# BRD9057A_SiWx917M_4-Layer_ExtSw_REF_DES_.net
KiCad netlist of a schematic drawn in Altium Designer
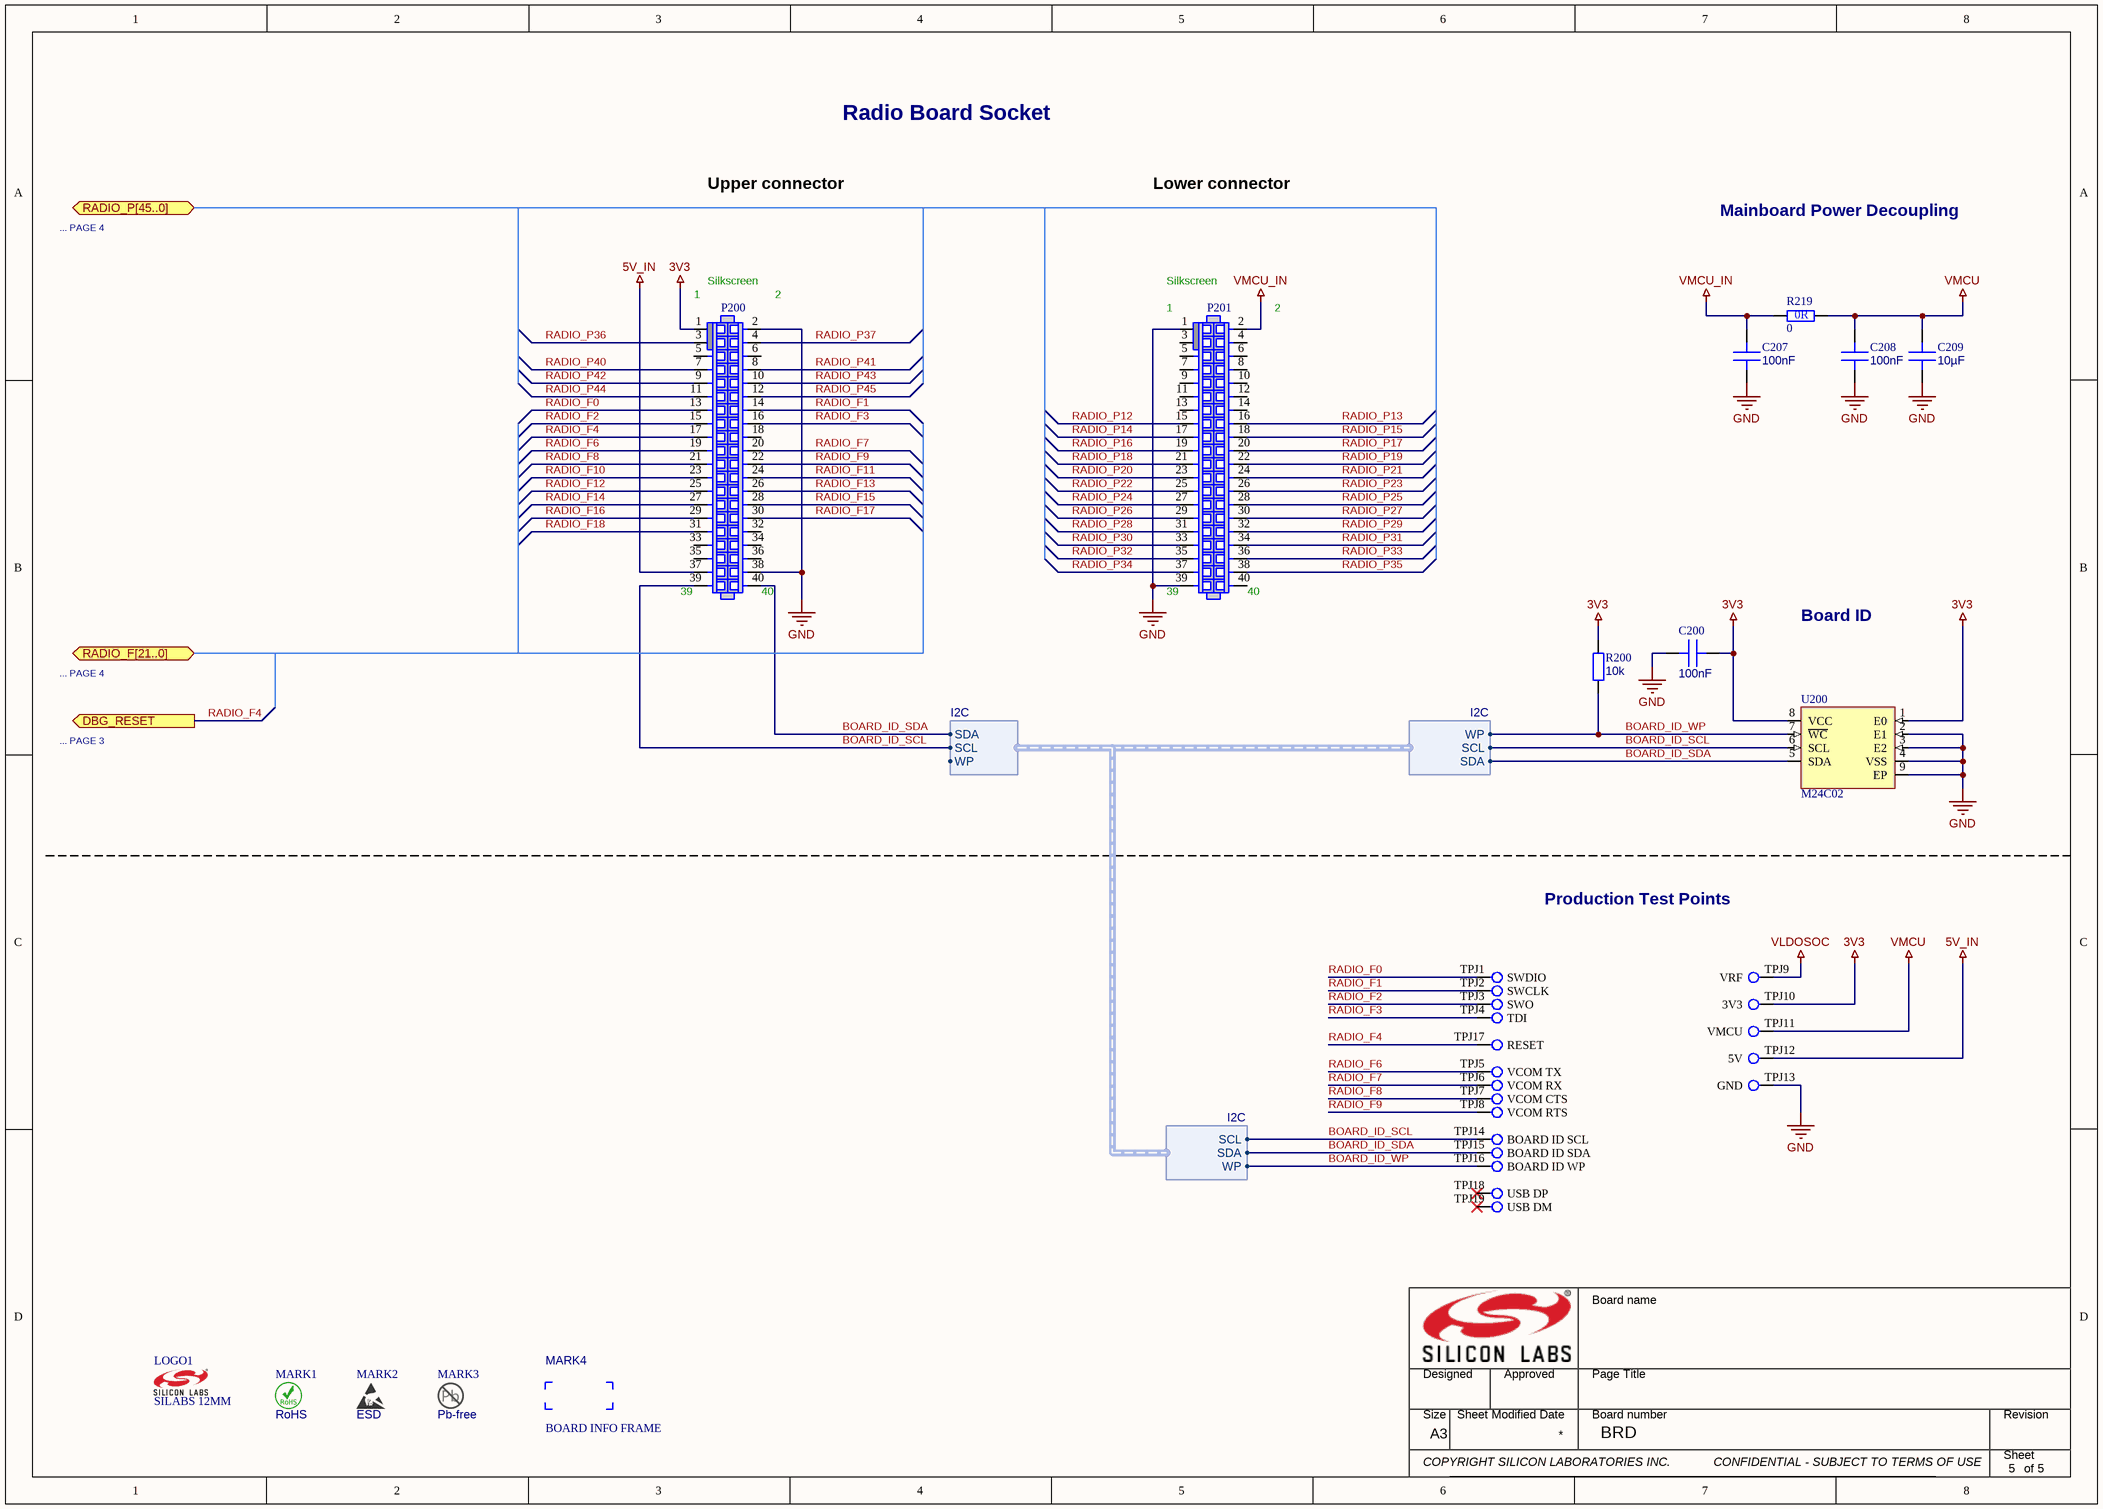
[diagram p0: BRD9057A_SiWx917M_4-Layer_ExtSw_REF_DES_A01_Page_5.SchDoc]

(export (version "E")
  (design (tool "Eeschema 10.0.6"))
  (components
    (comp (ref "C200")
      (value "100nF")
      (footprint "C0201_GM")
      (description "CAP CER 0201 X5R 100nF 16V 10%")
      (fields (field (name "TOLERANCE") "10%"))
      (libsource (lib "SiLabs Production Server") (part "Capacitor"))
    )
    (comp (ref "C207")
      (value "100nF")
      (footprint "C0201_GM")
      (description "CAP CER 0201 X5R 100nF 16V 10%")
      (fields (field (name "TOLERANCE") "10%"))
      (libsource (lib "SiLabs Production Server") (part "Capacitor"))
    )
    (comp (ref "C208")
      (value "100nF")
      (footprint "C0201_GM")
      (description "CAP CER 0201 X5R 100nF 16V 10%")
      (fields (field (name "TOLERANCE") "10%"))
      (libsource (lib "SiLabs Production Server") (part "Capacitor"))
    )
    (comp (ref "C209")
      (value "10µF")
      (footprint "C0603")
      (description "CAP CER 0603 X5R 10uF 16V 10%")
      (fields (field (name "TOLERANCE") "10%"))
      (libsource (lib "SiLabs Production Server") (part "Capacitor"))
    )
    (comp (ref "LOGO1")
      (value "SILABS 12MM")
      (footprint "LOGO_SILABS_W12.0_SILK")
      (description "Silkscreen logo, Silabs logo and text, B: 12MM, H:6MM")
      (fields (field (name "Comment") "LOGO SILABS 12MM"))
      (libsource (lib "SiLabs Production Server") (part "LOGO SILABS"))
    )
    (comp (ref "M1")
      (value "RB TEST FIXTURE PATTERN")
      (footprint "RB TEST FIXTURE PATTERN")
      (description "Subset of testpoints and keepouts for production test of Radio Boards")
      (libsource (lib "SiLabs Production Server") (part "RB FIXTURE PATTERN"))
    )
    (comp (ref "MARK1")
      (value "RoHS")
      (footprint "LOGO RoHS 5MM")
      (description "Silkscreen logo, RoHS, 5MM")
      (fields (field (name "Comment") "LOGO RoHS 5MM"))
      (libsource (lib "SiLabs Production Server") (part "LOGO RoHS"))
    )
    (comp (ref "MARK2")
      (value "ESD")
      (footprint "LOGO ESD 4.5MM")
      (description "Silkscreen logo, ESD, 4.5MM")
      (fields (field (name "Comment") "LOGO ESD 4.5MM"))
      (libsource (lib "SiLabs Production Server") (part "LOGO ESD"))
    )
    (comp (ref "MARK3")
      (value "Pb-free")
      (footprint "LOGO PBF 2MM")
      (description "Silkscreen logo, lead free, 2MM")
      (fields (field (name "Comment") "LOGO PBF 2MM"))
      (libsource (lib "SiLabs Production Server") (part "LOGO PBF"))
    )
    (comp (ref "MARK4")
      (value "BOARD INFO FRAME")
      (footprint "BOARD INFO FRAME SILK-Footprint-1")
      (description "Board info frame 19MM x 6MM, Silkscreen")
      (fields (field (name "Comment") "BOARD INFO FRAME 19MM"))
      (libsource (lib "SiLabs Production Server") (part "BOARD INFO FRAME"))
    )
    (comp (ref "P200")
      (value "2344-220MS3CUNR8")
      (footprint "SAMTEC_SFC-120-T2-L-D-A")
      (description "SOCKET 2X20 1.27MM SMD VRT KEYED")
      (fields (field (name "MANUFACTURER") "WCON"))
      (libsource (lib "SiLabs Production Server") (part "Header Female 2X20 with Notch"))
    )
    (comp (ref "P201")
      (value "2344-220MS3CUNR8")
      (footprint "SAMTEC_SFC-120-T2-L-D-A")
      (description "SOCKET 2X20 1.27MM SMD VRT KEYED")
      (fields (field (name "MANUFACTURER") "WCON"))
      (libsource (lib "SiLabs Production Server") (part "Header Female 2X20 with Notch"))
    )
    (comp (ref "R200")
      (value "10k")
      (footprint "R0201")
      (description "RES 0201 10K 1/20W 1% 200ppm")
      (fields (field (name "TOLERANCE") "1%"))
      (libsource (lib "SiLabs Production Server") (part "Resistor"))
    )
    (comp (ref "R219")
      (value "0")
      (footprint "R0402")
      (description "RES 0402 0R")
      (fields (field (name "TOLERANCE") "0%"))
      (libsource (lib "SiLabs Production Server") (part "Resistor-Jumper"))
    )
    (comp (ref "U200")
      (value "M24C02")
      (footprint "DFN50P300X200X60_HS-9N_GM")
      (description "IC EEPROM 2KBIT I2C UFDFPN8")
      (fields (field (name "VOLTAGE") "5.5V") (field (name "MANUFACTURER") "ST Microelectronics"))
      (libsource (lib "SiLabs Production Server") (part "M24C02-F"))
    )
  )
  (nets
    (net (code "6") (name "/BOARD_ID_SCL") (class "Default")
      (node (ref "M1") (pin "TPJ14") (pinfunction "BOARD_ID_SCL_TPJ14") (pintype "passive"))
      (node (ref "P200") (pin "39") (pinfunction "39_39") (pintype "passive"))
      (node (ref "U200") (pin "6") (pinfunction "SCL_6") (pintype "input"))
    )
    (net (code "7") (name "/BOARD_ID_SDA") (class "Default")
      (node (ref "M1") (pin "TPJ15") (pinfunction "BOARD_ID_SDA_TPJ15") (pintype "passive"))
      (node (ref "P200") (pin "40") (pinfunction "40_40") (pintype "passive"))
      (node (ref "U200") (pin "5") (pinfunction "SDA_5") (pintype "bidirectional"))
    )
    (net (code "8") (name "/BOARD_ID_WP") (class "Default")
      (node (ref "M1") (pin "TPJ16") (pinfunction "BOARD_ID_WP_TPJ16") (pintype "passive"))
      (node (ref "R200") (pin "1") (pinfunction "1_1") (pintype "passive"))
      (node (ref "U200") (pin "7") (pinfunction "~{WC}_7") (pintype "input"))
    )
    (net (code "9") (name "/RADIO_F0") (class "Default")
      (node (ref "M1") (pin "TPJ1") (pinfunction "SWDIO_TPJ1") (pintype "passive"))
      (node (ref "P200") (pin "13") (pinfunction "13_13") (pintype "passive"))
    )
    (net (code "10") (name "/RADIO_F1") (class "Default")
      (node (ref "M1") (pin "TPJ2") (pinfunction "SWCLK_TPJ2") (pintype "passive"))
      (node (ref "P200") (pin "14") (pinfunction "14_14") (pintype "passive"))
    )
    (net (code "11") (name "/RADIO_F2") (class "Default")
      (node (ref "M1") (pin "TPJ3") (pinfunction "SWO_TPJ3") (pintype "passive"))
      (node (ref "P200") (pin "15") (pinfunction "15_15") (pintype "passive"))
    )
    (net (code "12") (name "/RADIO_F3") (class "Default")
      (node (ref "M1") (pin "TPJ4") (pinfunction "TDI_TPJ4") (pintype "passive"))
      (node (ref "P200") (pin "16") (pinfunction "16_16") (pintype "passive"))
    )
    (net (code "13") (name "/RADIO_F4") (class "Default")
      (node (ref "M1") (pin "TPJ17") (pinfunction "RESET_TPJ17") (pintype "passive"))
      (node (ref "P200") (pin "17") (pinfunction "17_17") (pintype "passive"))
    )
    (net (code "14") (name "/RADIO_F6") (class "Default")
      (node (ref "M1") (pin "TPJ5") (pinfunction "VCOM_TX_TPJ5") (pintype "passive"))
      (node (ref "P200") (pin "19") (pinfunction "19_19") (pintype "passive"))
    )
    (net (code "15") (name "/RADIO_F7") (class "Default")
      (node (ref "M1") (pin "TPJ6") (pinfunction "VCOM_RX_TPJ6") (pintype "passive"))
      (node (ref "P200") (pin "20") (pinfunction "20_20") (pintype "passive"))
    )
    (net (code "16") (name "/RADIO_F8") (class "Default")
      (node (ref "M1") (pin "TPJ7") (pinfunction "VCOM_CTS_TPJ7") (pintype "passive"))
      (node (ref "P200") (pin "21") (pinfunction "21_21") (pintype "passive"))
    )
    (net (code "17") (name "/RADIO_F9") (class "Default")
      (node (ref "M1") (pin "TPJ8") (pinfunction "VCOM_RTS_TPJ8") (pintype "passive"))
      (node (ref "P200") (pin "22") (pinfunction "22_22") (pintype "passive"))
    )
    (net (code "18") (name "/RADIO_F10") (class "Default")
      (node (ref "P200") (pin "23") (pinfunction "23_23") (pintype "passive"))
    )
    (net (code "19") (name "/RADIO_F11") (class "Default")
      (node (ref "P200") (pin "24") (pinfunction "24_24") (pintype "passive"))
    )
    (net (code "20") (name "/RADIO_F12") (class "Default")
      (node (ref "P200") (pin "25") (pinfunction "25_25") (pintype "passive"))
    )
    (net (code "21") (name "/RADIO_F13") (class "Default")
      (node (ref "P200") (pin "26") (pinfunction "26_26") (pintype "passive"))
    )
    (net (code "22") (name "/RADIO_F14") (class "Default")
      (node (ref "P200") (pin "27") (pinfunction "27_27") (pintype "passive"))
    )
    (net (code "23") (name "/RADIO_F15") (class "Default")
      (node (ref "P200") (pin "28") (pinfunction "28_28") (pintype "passive"))
    )
    (net (code "24") (name "/RADIO_F16") (class "Default")
      (node (ref "P200") (pin "29") (pinfunction "29_29") (pintype "passive"))
    )
    (net (code "25") (name "/RADIO_F17") (class "Default")
      (node (ref "P200") (pin "30") (pinfunction "30_30") (pintype "passive"))
    )
    (net (code "26") (name "/RADIO_F18") (class "Default")
      (node (ref "P200") (pin "31") (pinfunction "31_31") (pintype "passive"))
    )
    (net (code "28") (name "/RADIO_P12") (class "Default")
      (node (ref "P201") (pin "15") (pinfunction "15_15") (pintype "passive"))
    )
    (net (code "29") (name "/RADIO_P13") (class "Default")
      (node (ref "P201") (pin "16") (pinfunction "16_16") (pintype "passive"))
    )
    (net (code "30") (name "/RADIO_P14") (class "Default")
      (node (ref "P201") (pin "17") (pinfunction "17_17") (pintype "passive"))
    )
    (net (code "31") (name "/RADIO_P15") (class "Default")
      (node (ref "P201") (pin "18") (pinfunction "18_18") (pintype "passive"))
    )
    (net (code "32") (name "/RADIO_P16") (class "Default")
      (node (ref "P201") (pin "19") (pinfunction "19_19") (pintype "passive"))
    )
    (net (code "33") (name "/RADIO_P17") (class "Default")
      (node (ref "P201") (pin "20") (pinfunction "20_20") (pintype "passive"))
    )
    (net (code "34") (name "/RADIO_P18") (class "Default")
      (node (ref "P201") (pin "21") (pinfunction "21_21") (pintype "passive"))
    )
    (net (code "35") (name "/RADIO_P19") (class "Default")
      (node (ref "P201") (pin "22") (pinfunction "22_22") (pintype "passive"))
    )
    (net (code "36") (name "/RADIO_P20") (class "Default")
      (node (ref "P201") (pin "23") (pinfunction "23_23") (pintype "passive"))
    )
    (net (code "37") (name "/RADIO_P21") (class "Default")
      (node (ref "P201") (pin "24") (pinfunction "24_24") (pintype "passive"))
    )
    (net (code "38") (name "/RADIO_P22") (class "Default")
      (node (ref "P201") (pin "25") (pinfunction "25_25") (pintype "passive"))
    )
    (net (code "39") (name "/RADIO_P23") (class "Default")
      (node (ref "P201") (pin "26") (pinfunction "26_26") (pintype "passive"))
    )
    (net (code "40") (name "/RADIO_P24") (class "Default")
      (node (ref "P201") (pin "27") (pinfunction "27_27") (pintype "passive"))
    )
    (net (code "41") (name "/RADIO_P25") (class "Default")
      (node (ref "P201") (pin "28") (pinfunction "28_28") (pintype "passive"))
    )
    (net (code "42") (name "/RADIO_P26") (class "Default")
      (node (ref "P201") (pin "29") (pinfunction "29_29") (pintype "passive"))
    )
    (net (code "43") (name "/RADIO_P27") (class "Default")
      (node (ref "P201") (pin "30") (pinfunction "30_30") (pintype "passive"))
    )
    (net (code "44") (name "/RADIO_P28") (class "Default")
      (node (ref "P201") (pin "31") (pinfunction "31_31") (pintype "passive"))
    )
    (net (code "45") (name "/RADIO_P29") (class "Default")
      (node (ref "P201") (pin "32") (pinfunction "32_32") (pintype "passive"))
    )
    (net (code "46") (name "/RADIO_P30") (class "Default")
      (node (ref "P201") (pin "33") (pinfunction "33_33") (pintype "passive"))
    )
    (net (code "47") (name "/RADIO_P31") (class "Default")
      (node (ref "P201") (pin "34") (pinfunction "34_34") (pintype "passive"))
    )
    (net (code "48") (name "/RADIO_P32") (class "Default")
      (node (ref "P201") (pin "35") (pinfunction "35_35") (pintype "passive"))
    )
    (net (code "49") (name "/RADIO_P33") (class "Default")
      (node (ref "P201") (pin "36") (pinfunction "36_36") (pintype "passive"))
    )
    (net (code "50") (name "/RADIO_P34") (class "Default")
      (node (ref "P201") (pin "37") (pinfunction "37_37") (pintype "passive"))
    )
    (net (code "51") (name "/RADIO_P35") (class "Default")
      (node (ref "P201") (pin "38") (pinfunction "38_38") (pintype "passive"))
    )
    (net (code "52") (name "/RADIO_P36") (class "Default")
      (node (ref "P200") (pin "3") (pinfunction "3_3") (pintype "passive"))
    )
    (net (code "53") (name "/RADIO_P37") (class "Default")
      (node (ref "P200") (pin "4") (pinfunction "4_4") (pintype "passive"))
    )
    (net (code "54") (name "/RADIO_P40") (class "Default")
      (node (ref "P200") (pin "7") (pinfunction "7_7") (pintype "passive"))
    )
    (net (code "55") (name "/RADIO_P41") (class "Default")
      (node (ref "P200") (pin "8") (pinfunction "8_8") (pintype "passive"))
    )
    (net (code "56") (name "/RADIO_P42") (class "Default")
      (node (ref "P200") (pin "9") (pinfunction "9_9") (pintype "passive"))
    )
    (net (code "57") (name "/RADIO_P43") (class "Default")
      (node (ref "P200") (pin "10") (pinfunction "10_10") (pintype "passive"))
    )
    (net (code "58") (name "/RADIO_P44") (class "Default")
      (node (ref "P200") (pin "11") (pinfunction "11_11") (pintype "passive"))
    )
    (net (code "59") (name "/RADIO_P45") (class "Default")
      (node (ref "P200") (pin "12") (pinfunction "12_12") (pintype "passive"))
    )
    (net (code "62") (name "3V3") (class "Default")
      (node (ref "C200") (pin "1") (pinfunction "1_1") (pintype "passive"))
      (node (ref "M1") (pin "TPJ10") (pinfunction "3V3_TPJ10") (pintype "passive"))
      (node (ref "P200") (pin "1") (pinfunction "1_1") (pintype "passive"))
      (node (ref "R200") (pin "2") (pinfunction "2_2") (pintype "passive"))
      (node (ref "U200") (pin "1") (pinfunction "E0_1") (pintype "input"))
      (node (ref "U200") (pin "8") (pinfunction "VCC_8") (pintype "power_in"))
    )
    (net (code "63") (name "5V_IN") (class "Default")
      (node (ref "M1") (pin "TPJ12") (pinfunction "5V_TPJ12") (pintype "passive"))
      (node (ref "P200") (pin "37") (pinfunction "37_37") (pintype "passive"))
    )
    (net (code "64") (name "GND") (class "Default")
      (node (ref "C200") (pin "2") (pinfunction "2_2") (pintype "passive"))
      (node (ref "C207") (pin "1") (pinfunction "1_1") (pintype "passive"))
      (node (ref "C208") (pin "1") (pinfunction "1_1") (pintype "passive"))
      (node (ref "C209") (pin "2") (pinfunction "2_2") (pintype "passive"))
      (node (ref "M1") (pin "TPJ13") (pinfunction "GND_TPJ13") (pintype "passive"))
      (node (ref "P200") (pin "2") (pinfunction "2_2") (pintype "passive"))
      (node (ref "P200") (pin "38") (pinfunction "38_38") (pintype "passive"))
      (node (ref "P201") (pin "1") (pinfunction "1_1") (pintype "passive"))
      (node (ref "P201") (pin "39") (pinfunction "39_39") (pintype "passive"))
      (node (ref "U200") (pin "2") (pinfunction "E1_2") (pintype "input"))
      (node (ref "U200") (pin "3") (pinfunction "E2_3") (pintype "input"))
      (node (ref "U200") (pin "4") (pinfunction "VSS_4") (pintype "power_in"))
      (node (ref "U200") (pin "9") (pinfunction "EP_9") (pintype "power_in"))
    )
    (net (code "65") (name "VLDOSOC") (class "Default")
      (node (ref "M1") (pin "TPJ9") (pinfunction "VRF_TPJ9") (pintype "passive"))
    )
    (net (code "66") (name "VMCU") (class "Default")
      (node (ref "C208") (pin "2") (pinfunction "2_2") (pintype "passive"))
      (node (ref "C209") (pin "1") (pinfunction "1_1") (pintype "passive"))
      (node (ref "M1") (pin "TPJ11") (pinfunction "VMCU_TPJ11") (pintype "passive"))
      (node (ref "R219") (pin "2") (pinfunction "2_2") (pintype "passive"))
    )
    (net (code "67") (name "VMCU_IN") (class "Default")
      (node (ref "C207") (pin "2") (pinfunction "2_2") (pintype "passive"))
      (node (ref "P201") (pin "2") (pinfunction "2_2") (pintype "passive"))
      (node (ref "R219") (pin "1") (pinfunction "1_1") (pintype "passive"))
    )
    (net (code "68") (name "unconnected-(M1-USB_DM-PadTPJ19)") (class "Default")
      (node (ref "M1") (pin "TPJ19") (pinfunction "USB_DM_TPJ19") (pintype "passive+no_connect"))
    )
    (net (code "69") (name "unconnected-(M1-USB_DP-PadTPJ18)") (class "Default")
      (node (ref "M1") (pin "TPJ18") (pinfunction "USB_DP_TPJ18") (pintype "passive+no_connect"))
    )
    (net (code "70") (name "unconnected-(P200-Pad5)") (class "Default")
      (node (ref "P200") (pin "5") (pinfunction "5_5") (pintype "passive"))
    )
    (net (code "71") (name "unconnected-(P200-Pad6)") (class "Default")
      (node (ref "P200") (pin "6") (pinfunction "6_6") (pintype "passive"))
    )
    (net (code "72") (name "unconnected-(P200-Pad18)") (class "Default")
      (node (ref "P200") (pin "18") (pinfunction "18_18") (pintype "passive"))
    )
    (net (code "73") (name "unconnected-(P200-Pad32)") (class "Default")
      (node (ref "P200") (pin "32") (pinfunction "32_32") (pintype "passive"))
    )
    (net (code "74") (name "unconnected-(P200-Pad33)") (class "Default")
      (node (ref "P200") (pin "33") (pinfunction "33_33") (pintype "passive"))
    )
    (net (code "75") (name "unconnected-(P200-Pad34)") (class "Default")
      (node (ref "P200") (pin "34") (pinfunction "34_34") (pintype "passive"))
    )
    (net (code "76") (name "unconnected-(P200-Pad35)") (class "Default")
      (node (ref "P200") (pin "35") (pinfunction "35_35") (pintype "passive"))
    )
    (net (code "77") (name "unconnected-(P200-Pad36)") (class "Default")
      (node (ref "P200") (pin "36") (pinfunction "36_36") (pintype "passive"))
    )
    (net (code "78") (name "unconnected-(P201-Pad3)") (class "Default")
      (node (ref "P201") (pin "3") (pinfunction "3_3") (pintype "passive"))
    )
    (net (code "79") (name "unconnected-(P201-Pad4)") (class "Default")
      (node (ref "P201") (pin "4") (pinfunction "4_4") (pintype "passive"))
    )
    (net (code "80") (name "unconnected-(P201-Pad5)") (class "Default")
      (node (ref "P201") (pin "5") (pinfunction "5_5") (pintype "passive"))
    )
    (net (code "81") (name "unconnected-(P201-Pad6)") (class "Default")
      (node (ref "P201") (pin "6") (pinfunction "6_6") (pintype "passive"))
    )
    (net (code "82") (name "unconnected-(P201-Pad7)") (class "Default")
      (node (ref "P201") (pin "7") (pinfunction "7_7") (pintype "passive"))
    )
    (net (code "83") (name "unconnected-(P201-Pad8)") (class "Default")
      (node (ref "P201") (pin "8") (pinfunction "8_8") (pintype "passive"))
    )
    (net (code "84") (name "unconnected-(P201-Pad9)") (class "Default")
      (node (ref "P201") (pin "9") (pinfunction "9_9") (pintype "passive"))
    )
    (net (code "85") (name "unconnected-(P201-Pad10)") (class "Default")
      (node (ref "P201") (pin "10") (pinfunction "10_10") (pintype "passive"))
    )
    (net (code "86") (name "unconnected-(P201-Pad11)") (class "Default")
      (node (ref "P201") (pin "11") (pinfunction "11_11") (pintype "passive"))
    )
    (net (code "87") (name "unconnected-(P201-Pad12)") (class "Default")
      (node (ref "P201") (pin "12") (pinfunction "12_12") (pintype "passive"))
    )
    (net (code "88") (name "unconnected-(P201-Pad13)") (class "Default")
      (node (ref "P201") (pin "13") (pinfunction "13_13") (pintype "passive"))
    )
    (net (code "89") (name "unconnected-(P201-Pad14)") (class "Default")
      (node (ref "P201") (pin "14") (pinfunction "14_14") (pintype "passive"))
    )
    (net (code "90") (name "unconnected-(P201-Pad40)") (class "Default")
      (node (ref "P201") (pin "40") (pinfunction "40_40") (pintype "passive"))
    )
  )
)
